# receiver.net
KiCad netlist of a schematic drawn in EAGLE
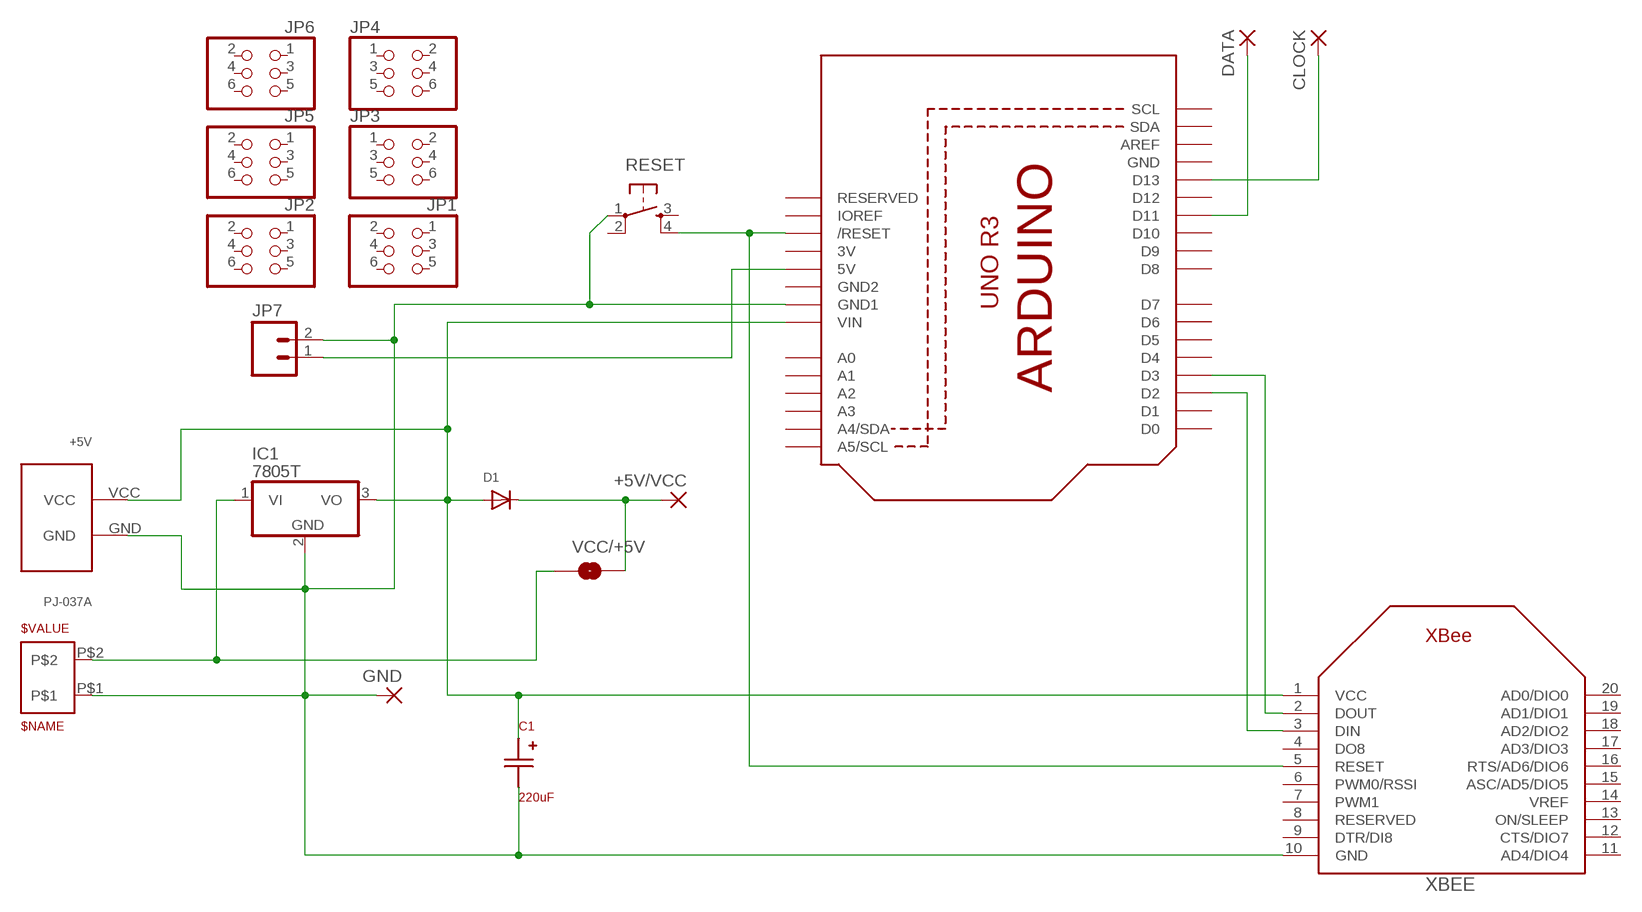
[diagram p0: schematic, sheet 1]

(export (version "E")
  (design (tool "Eeschema 10.0.6"))
  (components
    (comp (ref "+5V")
      (value "PJ-037A")
      (footprint "eagle-import:PJ-037A")
      (libsource (lib "eagle-import") (part "PJ-037A"))
    )
    (comp (ref "+5V/VCC")
      (value "2,15/1,0")
      (footprint "eagle-import:2,15_1,0")
      (libsource (lib "eagle-import") (part "2,15/1,0"))
    )
    (comp (ref "C1")
      (value "220uF")
      (footprint "eagle-import:UWT0J221MCL1GB")
      (libsource (lib "eagle-import") (part "UWT0J221MCL1GB"))
    )
    (comp (ref "CLOCK")
      (value "2,15/1,0")
      (footprint "eagle-import:2,15_1,0")
      (libsource (lib "eagle-import") (part "2,15/1,0"))
    )
    (comp (ref "D1")
      (value "DIODESOD-323F")
      (footprint "eagle-import:SOD-323F")
      (libsource (lib "eagle-import") (part "DIODESOD-323F"))
    )
    (comp (ref "DATA")
      (value "2,15/1,0")
      (footprint "eagle-import:2,15_1,0")
      (libsource (lib "eagle-import") (part "2,15/1,0"))
    )
    (comp (ref "GND")
      (value "2,15/1,0")
      (footprint "eagle-import:2,15_1,0")
      (libsource (lib "eagle-import") (part "2,15/1,0"))
    )
    (comp (ref "IC1")
      (value "7805T")
      (footprint "eagle-import:TO220H")
      (libsource (lib "eagle-import") (part "78T05"))
    )
    (comp (ref "JP1")
      (value "PINHD-2X3")
      (footprint "eagle-import:2X03")
      (libsource (lib "eagle-import") (part "PINHD-2X3"))
    )
    (comp (ref "JP2")
      (value "PINHD-2X3")
      (footprint "eagle-import:2X03")
      (libsource (lib "eagle-import") (part "PINHD-2X3"))
    )
    (comp (ref "JP3")
      (value "PINHD-2X3")
      (footprint "eagle-import:2X03")
      (libsource (lib "eagle-import") (part "PINHD-2X3"))
    )
    (comp (ref "JP4")
      (value "PINHD-2X3")
      (footprint "eagle-import:2X03")
      (libsource (lib "eagle-import") (part "PINHD-2X3"))
    )
    (comp (ref "JP5")
      (value "PINHD-2X3")
      (footprint "eagle-import:2X03")
      (libsource (lib "eagle-import") (part "PINHD-2X3"))
    )
    (comp (ref "JP6")
      (value "PINHD-2X3")
      (footprint "eagle-import:2X03")
      (libsource (lib "eagle-import") (part "PINHD-2X3"))
    )
    (comp (ref "JP7")
      (value "M02PTH")
      (footprint "eagle-import:1X02")
      (libsource (lib "eagle-import") (part "M02PTH"))
    )
    (comp (ref "RESET")
      (value "TAC_SWITCHSMD")
      (footprint "eagle-import:TACTILE_SWITCH_SMD")
      (libsource (lib "eagle-import") (part "TAC_SWITCHSMD"))
    )
    (comp (ref "U1")
      (value "ARDUINOR3-DIMENSION")
      (footprint "eagle-import:ARDUINOR3")
      (libsource (lib "eagle-import") (part "ARDUINOR3-DIMENSION"))
    )
    (comp (ref "VCC")
      (value "OSTOQ023251")
      (footprint "eagle-import:OSTOQ023251")
      (libsource (lib "eagle-import") (part "OSTOQ023251"))
    )
    (comp (ref "VCC/+5V")
      (value "NC=+5v")
      (footprint "eagle-import:SJ_2S-NO")
      (libsource (lib "eagle-import") (part "SOLDERJUMPERNO"))
    )
    (comp (ref "XBEE")
      (value "XBEE")
      (footprint "eagle-import:XBEE")
      (libsource (lib "eagle-import") (part "XBEE"))
    )
  )
  (nets
    (net (code "1") (name "/3V") (class "Default")
      (node (ref "U1") (pin "3V") (pinfunction "3V_3V") (pintype "power_in"))
    )
    (net (code "2") (name "/GND") (class "Default")
      (node (ref "U1") (pin "GND") (pinfunction "GND_GND") (pintype "power_in"))
    )
    (net (code "3") (name "/GND2") (class "Default")
      (node (ref "U1") (pin "GND2") (pinfunction "GND2_GND2") (pintype "power_in"))
    )
    (net (code "4") (name "Net-(+5V/VCC-P)") (class "Default")
      (node (ref "+5V/VCC") (pin "1") (pinfunction "P_1") (pintype "passive"))
      (node (ref "D1") (pin "C") (pinfunction "C_C") (pintype "passive"))
      (node (ref "VCC/+5V") (pin "2") (pinfunction "2_2") (pintype "passive"))
    )
    (net (code "5") (name "Net-(CLOCK-P)") (class "Default")
      (node (ref "CLOCK") (pin "1") (pinfunction "P_1") (pintype "passive"))
      (node (ref "U1") (pin "D13") (pinfunction "D13_D13") (pintype "bidirectional"))
    )
    (net (code "6") (name "Net-(DATA-P)") (class "Default")
      (node (ref "DATA") (pin "1") (pinfunction "P_1") (pintype "passive"))
      (node (ref "U1") (pin "D11") (pinfunction "D11_D11") (pintype "bidirectional"))
    )
    (net (code "7") (name "Net-(GND-P)") (class "Default")
      (node (ref "+5V") (pin "GND") (pinfunction "GND_GND") (pintype "power_in"))
      (node (ref "C1") (pin "-") (pinfunction "-_-") (pintype "bidirectional"))
      (node (ref "GND") (pin "1") (pinfunction "P_1") (pintype "passive"))
      (node (ref "IC1") (pin "2") (pinfunction "GND_2") (pintype "passive"))
      (node (ref "JP7") (pin "2") (pinfunction "2_2") (pintype "passive"))
      (node (ref "RESET") (pin "1") (pinfunction "1_1") (pintype "passive"))
      (node (ref "U1") (pin "GND1") (pinfunction "GND1_GND1") (pintype "power_in"))
      (node (ref "VCC") (pin "P$1") (pinfunction "P$1_P$1") (pintype "bidirectional"))
      (node (ref "XBEE") (pin "10") (pinfunction "GND_10") (pintype "power_in"))
    )
    (net (code "8") (name "Net-(IC1-VI)") (class "Default")
      (node (ref "IC1") (pin "1") (pinfunction "VI_1") (pintype "input"))
      (node (ref "VCC") (pin "P$2") (pinfunction "P$2_P$2") (pintype "bidirectional"))
      (node (ref "VCC/+5V") (pin "1") (pinfunction "1_1") (pintype "passive"))
    )
    (net (code "9") (name "Net-(IC1-VO)") (class "Default")
      (node (ref "+5V") (pin "VCC") (pinfunction "VCC_VCC") (pintype "power_in"))
      (node (ref "C1") (pin "+") (pinfunction "+_+") (pintype "bidirectional"))
      (node (ref "D1") (pin "A") (pinfunction "A_A") (pintype "passive"))
      (node (ref "IC1") (pin "3") (pinfunction "VO_3") (pintype "passive"))
      (node (ref "U1") (pin "VIN") (pinfunction "VIN_VIN") (pintype "power_in"))
      (node (ref "XBEE") (pin "1") (pinfunction "VCC_1") (pintype "power_in"))
    )
    (net (code "10") (name "Net-(JP7-Pad1)") (class "Default")
      (node (ref "JP7") (pin "1") (pinfunction "1_1") (pintype "passive"))
      (node (ref "U1") (pin "5V") (pinfunction "5V_5V") (pintype "power_in"))
    )
    (net (code "11") (name "Net-(U1-{slash}RESET)") (class "Default")
      (node (ref "RESET") (pin "4") (pinfunction "4_4") (pintype "passive"))
      (node (ref "U1") (pin "RESET") (pinfunction "/RESET_RESET") (pintype "bidirectional"))
      (node (ref "XBEE") (pin "5") (pinfunction "RESET_5") (pintype "input"))
    )
    (net (code "12") (name "Net-(XBEE-DIN)") (class "Default")
      (node (ref "U1") (pin "D2") (pinfunction "D2_D2") (pintype "bidirectional"))
      (node (ref "XBEE") (pin "3") (pinfunction "DIN_3") (pintype "input"))
    )
    (net (code "13") (name "Net-(XBEE-DOUT)") (class "Default")
      (node (ref "U1") (pin "D3") (pinfunction "D3_D3") (pintype "bidirectional"))
      (node (ref "XBEE") (pin "2") (pinfunction "DOUT_2") (pintype "output"))
    )
    (net (code "14") (name "unconnected-(JP1-Pad1)") (class "Default")
      (node (ref "JP1") (pin "1") (pinfunction "1_1") (pintype "passive"))
    )
    (net (code "15") (name "unconnected-(JP1-Pad2)") (class "Default")
      (node (ref "JP1") (pin "2") (pinfunction "2_2") (pintype "passive"))
    )
    (net (code "16") (name "unconnected-(JP1-Pad3)") (class "Default")
      (node (ref "JP1") (pin "3") (pinfunction "3_3") (pintype "passive"))
    )
    (net (code "17") (name "unconnected-(JP1-Pad4)") (class "Default")
      (node (ref "JP1") (pin "4") (pinfunction "4_4") (pintype "passive"))
    )
    (net (code "18") (name "unconnected-(JP1-Pad5)") (class "Default")
      (node (ref "JP1") (pin "5") (pinfunction "5_5") (pintype "passive"))
    )
    (net (code "19") (name "unconnected-(JP1-Pad6)") (class "Default")
      (node (ref "JP1") (pin "6") (pinfunction "6_6") (pintype "passive"))
    )
    (net (code "20") (name "unconnected-(JP2-Pad1)") (class "Default")
      (node (ref "JP2") (pin "1") (pinfunction "1_1") (pintype "passive"))
    )
    (net (code "21") (name "unconnected-(JP2-Pad2)") (class "Default")
      (node (ref "JP2") (pin "2") (pinfunction "2_2") (pintype "passive"))
    )
    (net (code "22") (name "unconnected-(JP2-Pad3)") (class "Default")
      (node (ref "JP2") (pin "3") (pinfunction "3_3") (pintype "passive"))
    )
    (net (code "23") (name "unconnected-(JP2-Pad4)") (class "Default")
      (node (ref "JP2") (pin "4") (pinfunction "4_4") (pintype "passive"))
    )
    (net (code "24") (name "unconnected-(JP2-Pad5)") (class "Default")
      (node (ref "JP2") (pin "5") (pinfunction "5_5") (pintype "passive"))
    )
    (net (code "25") (name "unconnected-(JP2-Pad6)") (class "Default")
      (node (ref "JP2") (pin "6") (pinfunction "6_6") (pintype "passive"))
    )
    (net (code "26") (name "unconnected-(JP3-Pad1)") (class "Default")
      (node (ref "JP3") (pin "1") (pinfunction "1_1") (pintype "passive"))
    )
    (net (code "27") (name "unconnected-(JP3-Pad2)") (class "Default")
      (node (ref "JP3") (pin "2") (pinfunction "2_2") (pintype "passive"))
    )
    (net (code "28") (name "unconnected-(JP3-Pad3)") (class "Default")
      (node (ref "JP3") (pin "3") (pinfunction "3_3") (pintype "passive"))
    )
    (net (code "29") (name "unconnected-(JP3-Pad4)") (class "Default")
      (node (ref "JP3") (pin "4") (pinfunction "4_4") (pintype "passive"))
    )
    (net (code "30") (name "unconnected-(JP3-Pad5)") (class "Default")
      (node (ref "JP3") (pin "5") (pinfunction "5_5") (pintype "passive"))
    )
    (net (code "31") (name "unconnected-(JP3-Pad6)") (class "Default")
      (node (ref "JP3") (pin "6") (pinfunction "6_6") (pintype "passive"))
    )
    (net (code "32") (name "unconnected-(JP4-Pad1)") (class "Default")
      (node (ref "JP4") (pin "1") (pinfunction "1_1") (pintype "passive"))
    )
    (net (code "33") (name "unconnected-(JP4-Pad2)") (class "Default")
      (node (ref "JP4") (pin "2") (pinfunction "2_2") (pintype "passive"))
    )
    (net (code "34") (name "unconnected-(JP4-Pad3)") (class "Default")
      (node (ref "JP4") (pin "3") (pinfunction "3_3") (pintype "passive"))
    )
    (net (code "35") (name "unconnected-(JP4-Pad4)") (class "Default")
      (node (ref "JP4") (pin "4") (pinfunction "4_4") (pintype "passive"))
    )
    (net (code "36") (name "unconnected-(JP4-Pad5)") (class "Default")
      (node (ref "JP4") (pin "5") (pinfunction "5_5") (pintype "passive"))
    )
    (net (code "37") (name "unconnected-(JP4-Pad6)") (class "Default")
      (node (ref "JP4") (pin "6") (pinfunction "6_6") (pintype "passive"))
    )
    (net (code "38") (name "unconnected-(JP5-Pad1)") (class "Default")
      (node (ref "JP5") (pin "1") (pinfunction "1_1") (pintype "passive"))
    )
    (net (code "39") (name "unconnected-(JP5-Pad2)") (class "Default")
      (node (ref "JP5") (pin "2") (pinfunction "2_2") (pintype "passive"))
    )
    (net (code "40") (name "unconnected-(JP5-Pad3)") (class "Default")
      (node (ref "JP5") (pin "3") (pinfunction "3_3") (pintype "passive"))
    )
    (net (code "41") (name "unconnected-(JP5-Pad4)") (class "Default")
      (node (ref "JP5") (pin "4") (pinfunction "4_4") (pintype "passive"))
    )
    (net (code "42") (name "unconnected-(JP5-Pad5)") (class "Default")
      (node (ref "JP5") (pin "5") (pinfunction "5_5") (pintype "passive"))
    )
    (net (code "43") (name "unconnected-(JP5-Pad6)") (class "Default")
      (node (ref "JP5") (pin "6") (pinfunction "6_6") (pintype "passive"))
    )
    (net (code "44") (name "unconnected-(JP6-Pad1)") (class "Default")
      (node (ref "JP6") (pin "1") (pinfunction "1_1") (pintype "passive"))
    )
    (net (code "45") (name "unconnected-(JP6-Pad2)") (class "Default")
      (node (ref "JP6") (pin "2") (pinfunction "2_2") (pintype "passive"))
    )
    (net (code "46") (name "unconnected-(JP6-Pad3)") (class "Default")
      (node (ref "JP6") (pin "3") (pinfunction "3_3") (pintype "passive"))
    )
    (net (code "47") (name "unconnected-(JP6-Pad4)") (class "Default")
      (node (ref "JP6") (pin "4") (pinfunction "4_4") (pintype "passive"))
    )
    (net (code "48") (name "unconnected-(JP6-Pad5)") (class "Default")
      (node (ref "JP6") (pin "5") (pinfunction "5_5") (pintype "passive"))
    )
    (net (code "49") (name "unconnected-(JP6-Pad6)") (class "Default")
      (node (ref "JP6") (pin "6") (pinfunction "6_6") (pintype "passive"))
    )
    (net (code "50") (name "unconnected-(RESET-Pad2)") (class "Default")
      (node (ref "RESET") (pin "2") (pinfunction "2_2") (pintype "passive"))
    )
    (net (code "51") (name "unconnected-(RESET-Pad3)") (class "Default")
      (node (ref "RESET") (pin "3") (pinfunction "3_3") (pintype "passive"))
    )
    (net (code "52") (name "unconnected-(U1-A4{slash}SDA-PadA4)") (class "Default")
      (node (ref "U1") (pin "A4") (pinfunction "A4/SDA_A4") (pintype "bidirectional"))
    )
    (net (code "53") (name "unconnected-(U1-A5{slash}SCL-PadA5)") (class "Default")
      (node (ref "U1") (pin "A5") (pinfunction "A5/SCL_A5") (pintype "bidirectional"))
    )
    (net (code "54") (name "unconnected-(U1-PadA0)") (class "Default")
      (node (ref "U1") (pin "A0") (pinfunction "A0_A0") (pintype "bidirectional"))
    )
    (net (code "55") (name "unconnected-(U1-PadA1)") (class "Default")
      (node (ref "U1") (pin "A1") (pinfunction "A1_A1") (pintype "bidirectional"))
    )
    (net (code "56") (name "unconnected-(U1-PadA2)") (class "Default")
      (node (ref "U1") (pin "A2") (pinfunction "A2_A2") (pintype "bidirectional"))
    )
    (net (code "57") (name "unconnected-(U1-PadA3)") (class "Default")
      (node (ref "U1") (pin "A3") (pinfunction "A3_A3") (pintype "bidirectional"))
    )
    (net (code "58") (name "unconnected-(U1-PadAREF)") (class "Default")
      (node (ref "U1") (pin "AREF") (pinfunction "AREF_AREF") (pintype "bidirectional"))
    )
    (net (code "59") (name "unconnected-(U1-PadD0)") (class "Default")
      (node (ref "U1") (pin "D0") (pinfunction "D0_D0") (pintype "bidirectional"))
    )
    (net (code "60") (name "unconnected-(U1-PadD1)") (class "Default")
      (node (ref "U1") (pin "D1") (pinfunction "D1_D1") (pintype "bidirectional"))
    )
    (net (code "61") (name "unconnected-(U1-PadD4)") (class "Default")
      (node (ref "U1") (pin "D4") (pinfunction "D4_D4") (pintype "bidirectional"))
    )
    (net (code "62") (name "unconnected-(U1-PadD5)") (class "Default")
      (node (ref "U1") (pin "D5") (pinfunction "D5_D5") (pintype "bidirectional"))
    )
    (net (code "63") (name "unconnected-(U1-PadD6)") (class "Default")
      (node (ref "U1") (pin "D6") (pinfunction "D6_D6") (pintype "bidirectional"))
    )
    (net (code "64") (name "unconnected-(U1-PadD7)") (class "Default")
      (node (ref "U1") (pin "D7") (pinfunction "D7_D7") (pintype "bidirectional"))
    )
    (net (code "65") (name "unconnected-(U1-PadD8)") (class "Default")
      (node (ref "U1") (pin "D8") (pinfunction "D8_D8") (pintype "bidirectional"))
    )
    (net (code "66") (name "unconnected-(U1-PadD9)") (class "Default")
      (node (ref "U1") (pin "D9") (pinfunction "D9_D9") (pintype "bidirectional"))
    )
    (net (code "67") (name "unconnected-(U1-PadD10)") (class "Default")
      (node (ref "U1") (pin "D10") (pinfunction "D10_D10") (pintype "bidirectional"))
    )
    (net (code "68") (name "unconnected-(U1-PadD12)") (class "Default")
      (node (ref "U1") (pin "D12") (pinfunction "D12_D12") (pintype "bidirectional"))
    )
    (net (code "69") (name "unconnected-(U1-PadIOREF)") (class "Default")
      (node (ref "U1") (pin "IOREF") (pinfunction "IOREF_IOREF") (pintype "output"))
    )
    (net (code "70") (name "unconnected-(U1-PadRESERVED)") (class "Default")
      (node (ref "U1") (pin "RESERVED") (pinfunction "RESERVED_RESERVED") (pintype "no_connect"))
    )
    (net (code "71") (name "unconnected-(U1-PadSCL)") (class "Default")
      (node (ref "U1") (pin "SCL") (pinfunction "SCL_SCL") (pintype "bidirectional"))
    )
    (net (code "72") (name "unconnected-(U1-PadSDA)") (class "Default")
      (node (ref "U1") (pin "SDA") (pinfunction "SDA_SDA") (pintype "bidirectional"))
    )
    (net (code "73") (name "unconnected-(XBEE-AD0{slash}DIO0-Pad20)") (class "Default")
      (node (ref "XBEE") (pin "20") (pinfunction "AD0/DIO0_20") (pintype "bidirectional"))
    )
    (net (code "74") (name "unconnected-(XBEE-AD1{slash}DIO1-Pad19)") (class "Default")
      (node (ref "XBEE") (pin "19") (pinfunction "AD1/DIO1_19") (pintype "bidirectional"))
    )
    (net (code "75") (name "unconnected-(XBEE-AD2{slash}DIO2-Pad18)") (class "Default")
      (node (ref "XBEE") (pin "18") (pinfunction "AD2/DIO2_18") (pintype "bidirectional"))
    )
    (net (code "76") (name "unconnected-(XBEE-AD3{slash}DIO3-Pad17)") (class "Default")
      (node (ref "XBEE") (pin "17") (pinfunction "AD3/DIO3_17") (pintype "bidirectional"))
    )
    (net (code "77") (name "unconnected-(XBEE-AD4{slash}DIO4-Pad11)") (class "Default")
      (node (ref "XBEE") (pin "11") (pinfunction "AD4/DIO4_11") (pintype "bidirectional"))
    )
    (net (code "78") (name "unconnected-(XBEE-ASC{slash}AD5{slash}DIO5-Pad15)") (class "Default")
      (node (ref "XBEE") (pin "15") (pinfunction "ASC/AD5/DIO5_15") (pintype "bidirectional"))
    )
    (net (code "79") (name "unconnected-(XBEE-CTS{slash}DIO7-Pad12)") (class "Default")
      (node (ref "XBEE") (pin "12") (pinfunction "CTS/DIO7_12") (pintype "bidirectional"))
    )
    (net (code "80") (name "unconnected-(XBEE-DO8-Pad4)") (class "Default")
      (node (ref "XBEE") (pin "4") (pinfunction "DO8_4") (pintype "output"))
    )
    (net (code "81") (name "unconnected-(XBEE-DTR{slash}DI8-Pad9)") (class "Default")
      (node (ref "XBEE") (pin "9") (pinfunction "DTR/DI8_9") (pintype "input"))
    )
    (net (code "82") (name "unconnected-(XBEE-ON{slash}SLEEP-Pad13)") (class "Default")
      (node (ref "XBEE") (pin "13") (pinfunction "ON/SLEEP_13") (pintype "output"))
    )
    (net (code "83") (name "unconnected-(XBEE-PWM0{slash}RSSI-Pad6)") (class "Default")
      (node (ref "XBEE") (pin "6") (pinfunction "PWM0/RSSI_6") (pintype "output"))
    )
    (net (code "84") (name "unconnected-(XBEE-PWM1-Pad7)") (class "Default")
      (node (ref "XBEE") (pin "7") (pinfunction "PWM1_7") (pintype "output"))
    )
    (net (code "85") (name "unconnected-(XBEE-RESERVED-Pad8)") (class "Default")
      (node (ref "XBEE") (pin "8") (pinfunction "RESERVED_8") (pintype "no_connect"))
    )
    (net (code "86") (name "unconnected-(XBEE-RTS{slash}AD6{slash}DIO6-Pad16)") (class "Default")
      (node (ref "XBEE") (pin "16") (pinfunction "RTS/AD6/DIO6_16") (pintype "bidirectional"))
    )
    (net (code "87") (name "unconnected-(XBEE-VREF-Pad14)") (class "Default")
      (node (ref "XBEE") (pin "14") (pinfunction "VREF_14") (pintype "input"))
    )
  )
)
